# ICSP_Pogo_Connector.net
KiCad netlist of a schematic drawn in EAGLE
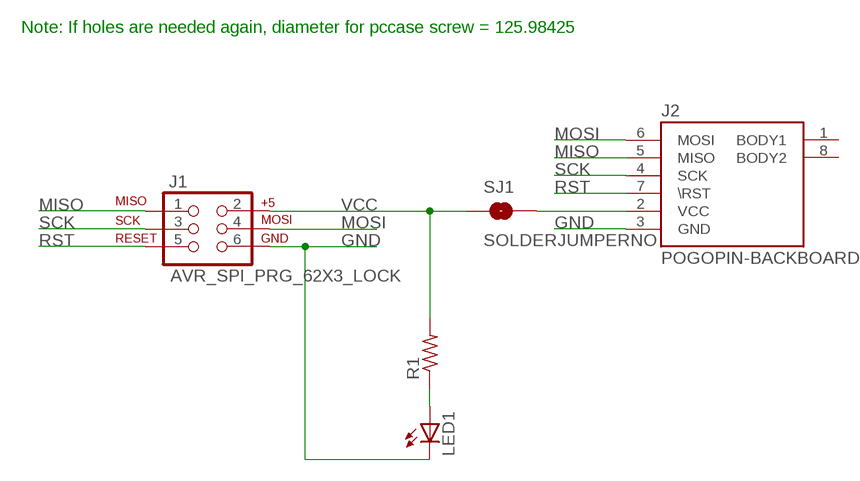
[diagram p0: schematic, sheet 1]

(export (version "E")
  (design (tool "Eeschema 10.0.6"))
  (components
    (comp (ref "J1")
      (value "AVR_SPI_PRG_62X3_LOCK")
      (footprint "eagle-import:2X3_LOCK")
      (libsource (lib "eagle-import") (part "AVR_SPI_PRG_62X3_LOCK"))
    )
    (comp (ref "J2")
      (value "POGOPIN-BACKBOARD")
      (footprint "eagle-import:POGOPROG-BACKMOUNT")
      (libsource (lib "eagle-import") (part "POGOPIN-BACKBOARD"))
    )
    (comp (ref "LED1")
      (value "LED0603")
      (footprint "eagle-import:LED-0603")
      (libsource (lib "eagle-import") (part "LED0603"))
    )
    (comp (ref "R1")
      (value "R-US_R0603")
      (footprint "eagle-import:R0603")
      (libsource (lib "eagle-import") (part "R-US_R0603"))
    )
    (comp (ref "SJ1")
      (value "SOLDERJUMPERNO")
      (footprint "eagle-import:SJ_2S-NO")
      (libsource (lib "eagle-import") (part "SOLDERJUMPERNO"))
    )
  )
  (nets
    (net (code "1") (name "/GND") (class "Default")
      (node (ref "J1") (pin "6") (pinfunction "6_6") (pintype "passive"))
      (node (ref "J2") (pin "3") (pinfunction "GND_3") (pintype "bidirectional"))
      (node (ref "LED1") (pin "C") (pinfunction "C_C") (pintype "passive"))
    )
    (net (code "2") (name "/MISO") (class "Default")
      (node (ref "J1") (pin "1") (pinfunction "1_1") (pintype "passive"))
      (node (ref "J2") (pin "5") (pinfunction "MISO_5") (pintype "bidirectional"))
    )
    (net (code "3") (name "/MOSI") (class "Default")
      (node (ref "J1") (pin "4") (pinfunction "4_4") (pintype "passive"))
      (node (ref "J2") (pin "6") (pinfunction "MOSI_6") (pintype "bidirectional"))
    )
    (net (code "4") (name "/RST") (class "Default")
      (node (ref "J1") (pin "5") (pinfunction "5_5") (pintype "passive"))
      (node (ref "J2") (pin "7") (pinfunction "\\RST_7") (pintype "bidirectional"))
    )
    (net (code "5") (name "/SCK") (class "Default")
      (node (ref "J1") (pin "3") (pinfunction "3_3") (pintype "passive"))
      (node (ref "J2") (pin "4") (pinfunction "SCK_4") (pintype "bidirectional"))
    )
    (net (code "6") (name "/VCC") (class "Default")
      (node (ref "J1") (pin "2") (pinfunction "2_2") (pintype "passive"))
      (node (ref "R1") (pin "2") (pinfunction "2_2") (pintype "passive"))
      (node (ref "SJ1") (pin "1") (pinfunction "1_1") (pintype "passive"))
    )
    (net (code "7") (name "Net-(J2-VCC)") (class "Default")
      (node (ref "J2") (pin "2") (pinfunction "VCC_2") (pintype "bidirectional"))
      (node (ref "SJ1") (pin "2") (pinfunction "2_2") (pintype "passive"))
    )
    (net (code "8") (name "Net-(LED1-PadA)") (class "Default")
      (node (ref "LED1") (pin "A") (pinfunction "A_A") (pintype "passive"))
      (node (ref "R1") (pin "1") (pinfunction "1_1") (pintype "passive"))
    )
    (net (code "9") (name "unconnected-(J2-BODY1-Pad1)") (class "Default")
      (node (ref "J2") (pin "1") (pinfunction "BODY1_1") (pintype "bidirectional"))
    )
    (net (code "10") (name "unconnected-(J2-BODY2-Pad8)") (class "Default")
      (node (ref "J2") (pin "8") (pinfunction "BODY2_8") (pintype "bidirectional"))
    )
  )
)
